# ov7670.net
KiCad netlist of a schematic drawn in EAGLE
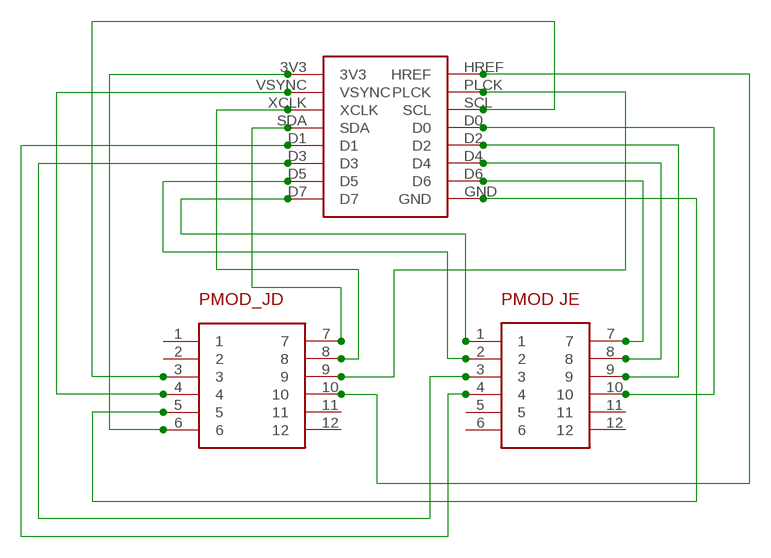
[diagram p0: schematic, sheet 1]

(export (version "E")
  (design (tool "Eeschema 10.0.6"))
  (components
    (comp (ref "U$1")
      (value "OV7670")
      (footprint "eagle-import:OV7670")
      (libsource (lib "eagle-import") (part "OV7670"))
    )
    (comp (ref "U$2")
      (value "PMOD_JD")
      (footprint "eagle-import:PMOD_JD")
      (libsource (lib "eagle-import") (part "PMOD_JD"))
    )
    (comp (ref "U$3")
      (value "PMOD_JE")
      (footprint "eagle-import:PMOD_JE")
      (libsource (lib "eagle-import") (part "PMOD_JE"))
    )
  )
  (nets
    (net (code "1") (name "Net-(U$1-Pad3V3)") (class "Default")
      (node (ref "U$1") (pin "3V3") (pinfunction "3V3_3V3") (pintype "bidirectional"))
      (node (ref "U$2") (pin "6") (pinfunction "6_6") (pintype "bidirectional"))
    )
    (net (code "2") (name "Net-(U$1-PadD0)") (class "Default")
      (node (ref "U$1") (pin "D0") (pinfunction "D0_D0") (pintype "bidirectional"))
      (node (ref "U$3") (pin "10") (pinfunction "10_10") (pintype "bidirectional"))
    )
    (net (code "3") (name "Net-(U$1-PadD1)") (class "Default")
      (node (ref "U$1") (pin "D1") (pinfunction "D1_D1") (pintype "bidirectional"))
      (node (ref "U$3") (pin "4") (pinfunction "4_4") (pintype "bidirectional"))
    )
    (net (code "4") (name "Net-(U$1-PadD2)") (class "Default")
      (node (ref "U$1") (pin "D2") (pinfunction "D2_D2") (pintype "bidirectional"))
      (node (ref "U$3") (pin "9") (pinfunction "9_9") (pintype "bidirectional"))
    )
    (net (code "5") (name "Net-(U$1-PadD3)") (class "Default")
      (node (ref "U$1") (pin "D3") (pinfunction "D3_D3") (pintype "bidirectional"))
      (node (ref "U$3") (pin "3") (pinfunction "3_3") (pintype "bidirectional"))
    )
    (net (code "6") (name "Net-(U$1-PadD4)") (class "Default")
      (node (ref "U$1") (pin "D4") (pinfunction "D4_D4") (pintype "bidirectional"))
      (node (ref "U$3") (pin "8") (pinfunction "8_8") (pintype "bidirectional"))
    )
    (net (code "7") (name "Net-(U$1-PadD5)") (class "Default")
      (node (ref "U$1") (pin "D5") (pinfunction "D5_D5") (pintype "bidirectional"))
      (node (ref "U$3") (pin "2") (pinfunction "2_2") (pintype "bidirectional"))
    )
    (net (code "8") (name "Net-(U$1-PadD6)") (class "Default")
      (node (ref "U$1") (pin "D6") (pinfunction "D6_D6") (pintype "bidirectional"))
      (node (ref "U$3") (pin "7") (pinfunction "7_7") (pintype "bidirectional"))
    )
    (net (code "9") (name "Net-(U$1-PadD7)") (class "Default")
      (node (ref "U$1") (pin "D7") (pinfunction "D7_D7") (pintype "bidirectional"))
      (node (ref "U$3") (pin "1") (pinfunction "1_1") (pintype "bidirectional"))
    )
    (net (code "10") (name "Net-(U$1-PadGND)") (class "Default")
      (node (ref "U$1") (pin "GND") (pinfunction "GND_GND") (pintype "bidirectional"))
      (node (ref "U$2") (pin "5") (pinfunction "5_5") (pintype "bidirectional"))
    )
    (net (code "11") (name "Net-(U$1-PadHREF)") (class "Default")
      (node (ref "U$1") (pin "HREF") (pinfunction "HREF_HREF") (pintype "bidirectional"))
      (node (ref "U$2") (pin "10") (pinfunction "10_10") (pintype "bidirectional"))
    )
    (net (code "12") (name "Net-(U$1-PadPLCK)") (class "Default")
      (node (ref "U$1") (pin "PLCK") (pinfunction "PLCK_PLCK") (pintype "bidirectional"))
      (node (ref "U$2") (pin "9") (pinfunction "9_9") (pintype "bidirectional"))
    )
    (net (code "13") (name "Net-(U$1-PadSCL)") (class "Default")
      (node (ref "U$1") (pin "SCL") (pinfunction "SCL_SCL") (pintype "bidirectional"))
      (node (ref "U$2") (pin "3") (pinfunction "3_3") (pintype "bidirectional"))
    )
    (net (code "14") (name "Net-(U$1-PadSDA)") (class "Default")
      (node (ref "U$1") (pin "SDA") (pinfunction "SDA_SDA") (pintype "bidirectional"))
      (node (ref "U$2") (pin "7") (pinfunction "7_7") (pintype "bidirectional"))
    )
    (net (code "15") (name "Net-(U$1-PadVSYNC)") (class "Default")
      (node (ref "U$1") (pin "VSYNC") (pinfunction "VSYNC_VSYNC") (pintype "bidirectional"))
      (node (ref "U$2") (pin "4") (pinfunction "4_4") (pintype "bidirectional"))
    )
    (net (code "16") (name "Net-(U$1-PadXCLK)") (class "Default")
      (node (ref "U$1") (pin "XCLK") (pinfunction "XCLK_XCLK") (pintype "bidirectional"))
      (node (ref "U$2") (pin "8") (pinfunction "8_8") (pintype "bidirectional"))
    )
    (net (code "17") (name "unconnected-(U$2-Pad1)") (class "Default")
      (node (ref "U$2") (pin "1") (pinfunction "1_1") (pintype "bidirectional"))
    )
    (net (code "18") (name "unconnected-(U$2-Pad2)") (class "Default")
      (node (ref "U$2") (pin "2") (pinfunction "2_2") (pintype "bidirectional"))
    )
    (net (code "19") (name "unconnected-(U$2-Pad11)") (class "Default")
      (node (ref "U$2") (pin "11") (pinfunction "11_11") (pintype "bidirectional"))
    )
    (net (code "20") (name "unconnected-(U$2-Pad12)") (class "Default")
      (node (ref "U$2") (pin "12") (pinfunction "12_12") (pintype "bidirectional"))
    )
    (net (code "21") (name "unconnected-(U$3-Pad5)") (class "Default")
      (node (ref "U$3") (pin "5") (pinfunction "5_5") (pintype "bidirectional"))
    )
    (net (code "22") (name "unconnected-(U$3-Pad6)") (class "Default")
      (node (ref "U$3") (pin "6") (pinfunction "6_6") (pintype "bidirectional"))
    )
    (net (code "23") (name "unconnected-(U$3-Pad11)") (class "Default")
      (node (ref "U$3") (pin "11") (pinfunction "11_11") (pintype "bidirectional"))
    )
    (net (code "24") (name "unconnected-(U$3-Pad12)") (class "Default")
      (node (ref "U$3") (pin "12") (pinfunction "12_12") (pintype "bidirectional"))
    )
  )
)
